# current_sensors.net
KiCad netlist of a schematic drawn in Altium Designer
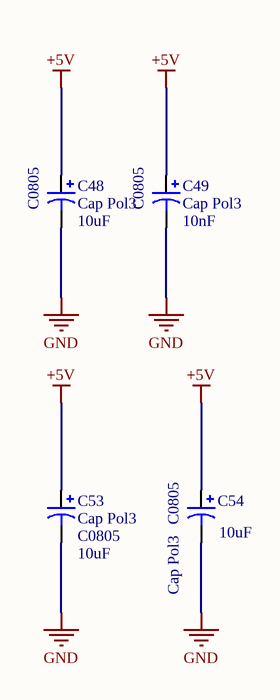
[diagram p0: current sensors.SchDoc]

(export (version "E")
  (design (tool "Eeschema 10.0.6"))
  (components
    (comp (ref "C48")
      (value "Cap Pol3")
      (footprint "C0805")
      (description "Polarized Capacitor (Surface Mount)")
      (fields
        (field (name "PACKAGEREFERENCE") "C0805")
        (field (name "ALTIUM_VALUE") "10uF")
        (field (name "PUBLISHER") "Altium Limited")
      )
      (libsource (lib "Miscellaneous Devices") (part "Cap Pol3"))
    )
    (comp (ref "C49")
      (value "Cap Pol3")
      (footprint "C0805")
      (description "Polarized Capacitor (Surface Mount)")
      (fields
        (field (name "PACKAGEREFERENCE") "C0805")
        (field (name "ALTIUM_VALUE") "10nF")
        (field (name "PUBLISHER") "Altium Limited")
      )
      (libsource (lib "Miscellaneous Devices") (part "Cap Pol3"))
    )
    (comp (ref "C53")
      (value "Cap Pol3")
      (footprint "C0805")
      (description "Polarized Capacitor (Surface Mount)")
      (fields
        (field (name "PACKAGEREFERENCE") "C0805")
        (field (name "ALTIUM_VALUE") "10uF")
        (field (name "PUBLISHER") "Altium Limited")
      )
      (libsource (lib "Miscellaneous Devices") (part "Cap Pol3"))
    )
    (comp (ref "C54")
      (value "Cap Pol3")
      (footprint "C0805")
      (description "Polarized Capacitor (Surface Mount)")
      (fields
        (field (name "PACKAGEREFERENCE") "C0805")
        (field (name "ALTIUM_VALUE") "10uF")
        (field (name "PUBLISHER") "Altium Limited")
      )
      (libsource (lib "Miscellaneous Devices") (part "Cap Pol3"))
    )
  )
  (nets
    (net (code "1") (name "+5V") (class "Default")
      (node (ref "C48") (pin "1") (pinfunction "1_1") (pintype "passive"))
      (node (ref "C49") (pin "1") (pinfunction "1_1") (pintype "passive"))
      (node (ref "C53") (pin "1") (pinfunction "1_1") (pintype "passive"))
      (node (ref "C54") (pin "1") (pinfunction "1_1") (pintype "passive"))
    )
    (net (code "2") (name "GND") (class "Default")
      (node (ref "C48") (pin "2") (pinfunction "2_2") (pintype "passive"))
      (node (ref "C49") (pin "2") (pinfunction "2_2") (pintype "passive"))
      (node (ref "C53") (pin "2") (pinfunction "2_2") (pintype "passive"))
      (node (ref "C54") (pin "2") (pinfunction "2_2") (pintype "passive"))
    )
  )
)
